# HF.net
KiCad netlist of a schematic drawn in Altium Designer
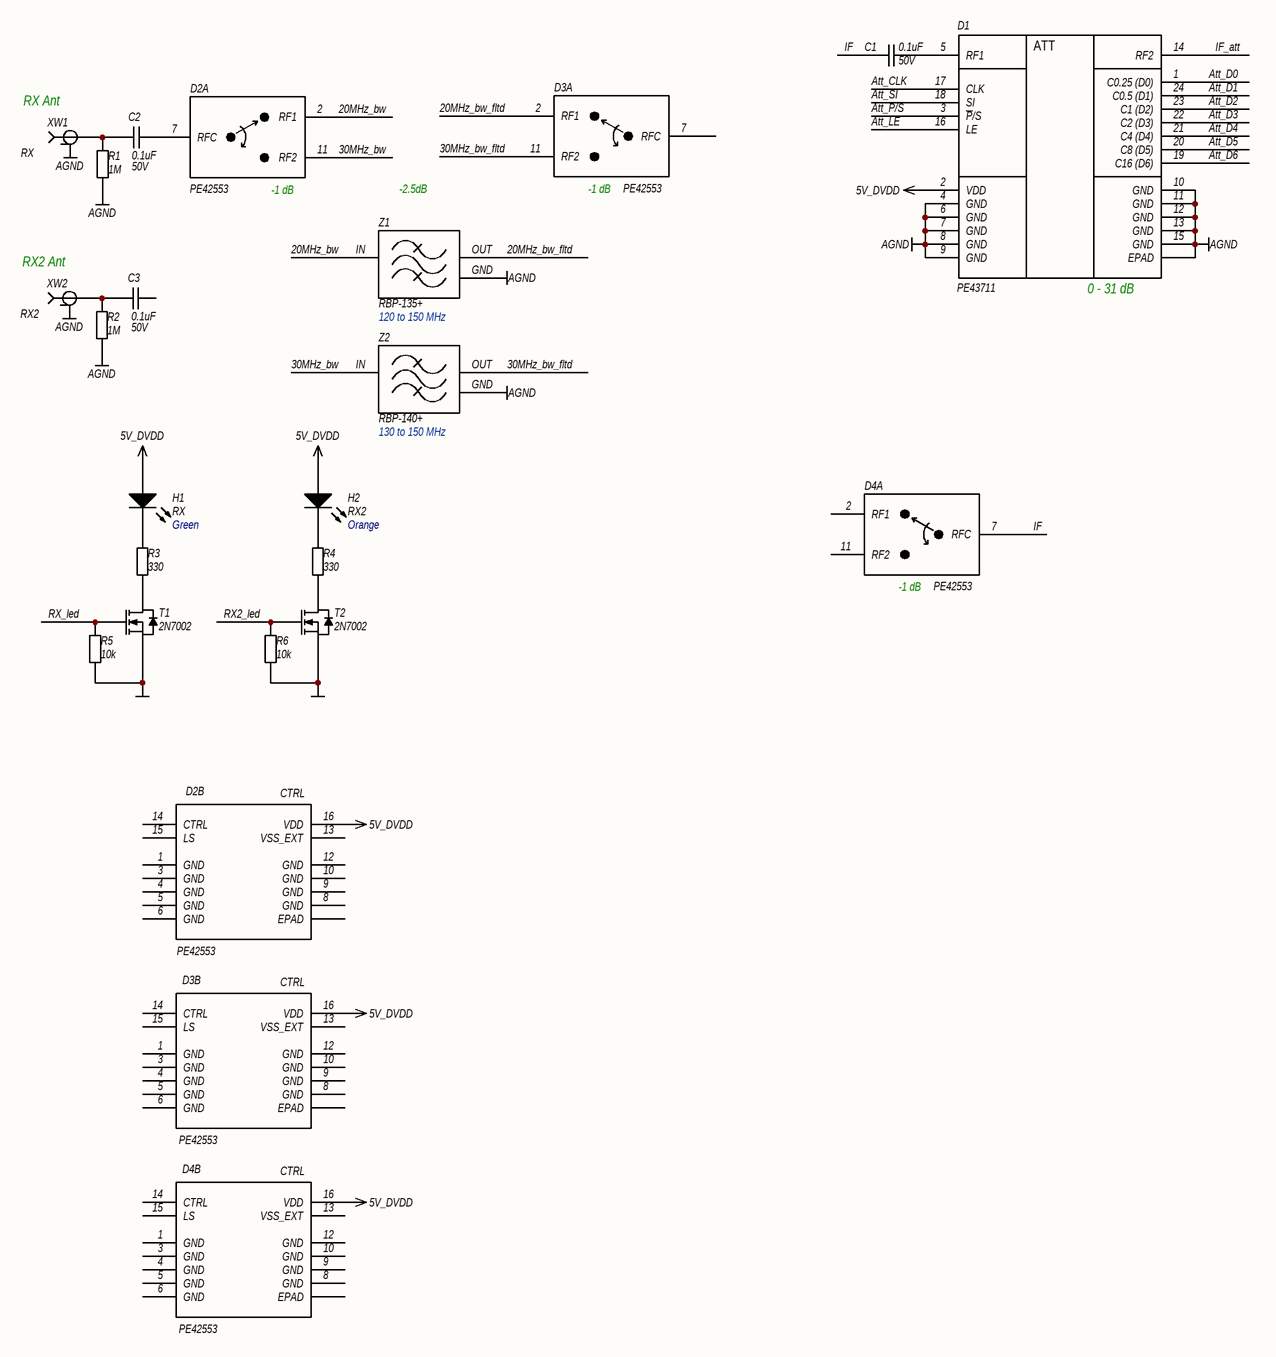
[diagram p0: HF.SchDoc]

(export (version "E")
  (design (tool "Eeschema 10.0.6"))
  (components
    (comp (ref "C1")
      (value "0.1uF")
      (footprint "C0402")
      (description "SMD Capacitor")
      (fields
        (field (name "MANUFACTURER") "Murata")
        (field (name "TOLERANCE") "10%")
        (field (name "VOLTAGE") "50V")
      )
      (libsource (lib "Kintex_SDR") (part "CAP"))
    )
    (comp (ref "C2")
      (value "0.1uF")
      (footprint "C0402")
      (description "SMD Capacitor")
      (fields
        (field (name "MANUFACTURER") "Murata")
        (field (name "TOLERANCE") "10%")
        (field (name "VOLTAGE") "50V")
      )
      (libsource (lib "Kintex_SDR") (part "CAP"))
    )
    (comp (ref "C3")
      (value "0.1uF")
      (footprint "C0402")
      (description "SMD Capacitor")
      (fields
        (field (name "MANUFACTURER") "Murata")
        (field (name "TOLERANCE") "10%")
        (field (name "VOLTAGE") "50V")
      )
      (libsource (lib "Kintex_SDR") (part "CAP"))
    )
    (comp (ref "D1")
      (value "PE43711")
      (footprint "QFN-24")
      (description "The PE43711 is a 50Ω, HaRP™ technology-enhanced, 7-bit RF digital step attenuator")
      (fields (field (name "MANUFACTURER") "Peregrine Technical Solutions"))
      (libsource (lib "DBLib") (part "PE43711"))
    )
    (comp (ref "D2")
      (value "PE42553")
      (footprint "QFN-16")
      (description "HaRPTM technology-enhanced absorptive SPDT")
      (fields (field (name "MANUFACTURER") "Peregrine Technical Solutions"))
      (libsource (lib "DBLib") (part "PE42553"))
    )
    (comp (ref "D3")
      (value "PE42553")
      (footprint "QFN-16")
      (description "HaRPTM technology-enhanced absorptive SPDT")
      (fields (field (name "MANUFACTURER") "Peregrine Technical Solutions"))
      (libsource (lib "") (part "PE42553_1"))
    )
    (comp (ref "D4")
      (value "PE42553")
      (footprint "QFN-16")
      (description "HaRPTM technology-enhanced absorptive SPDT")
      (fields (field (name "MANUFACTURER") "Peregrine Technical Solutions"))
      (libsource (lib "DBLib") (part "PE42553"))
    )
    (comp (ref "H1")
      (value "RX")
      (footprint "LED")
      (description "CHIP LED LAMP")
      (fields (field (name "MANUFACTURER") "Kingbright") (field (name "COLOR") "Green"))
      (libsource (lib "DBLib") (part "LED"))
    )
    (comp (ref "H2")
      (value "RX2")
      (footprint "LED")
      (description "CHIP LED LAMP")
      (fields (field (name "MANUFACTURER") "Kingbright") (field (name "COLOR") "Orange"))
      (libsource (lib "DBLib") (part "LED"))
    )
    (comp (ref "R1")
      (value "1M")
      (footprint "R0402")
      (description "SMD Resistor")
      (fields (field (name "POWER") "0.1 Wt") (field (name "TOLERANCE") "5%"))
      (libsource (lib "Kintex_SDR") (part "RES"))
    )
    (comp (ref "R2")
      (value "1M")
      (footprint "R0402")
      (description "SMD Resistor")
      (fields (field (name "POWER") "0.1 Wt") (field (name "TOLERANCE") "5%"))
      (libsource (lib "Kintex_SDR") (part "RES"))
    )
    (comp (ref "R3")
      (value "330")
      (footprint "R0805")
      (description "SMD Resistor")
      (fields (field (name "POWER") "0.125 Wt") (field (name "TOLERANCE") "5%"))
      (libsource (lib "Kintex_SDR") (part "RES"))
    )
    (comp (ref "R4")
      (value "330")
      (footprint "R0805")
      (description "SMD Resistor")
      (fields (field (name "POWER") "0.125 Wt") (field (name "TOLERANCE") "5%"))
      (libsource (lib "Kintex_SDR") (part "RES"))
    )
    (comp (ref "R5")
      (value "10k")
      (footprint "R0402")
      (description "SMD Resistor")
      (fields (field (name "POWER") "0.1 Wt") (field (name "TOLERANCE") "5%"))
      (libsource (lib "Kintex_SDR") (part "RES"))
    )
    (comp (ref "R6")
      (value "10k")
      (footprint "R0402")
      (description "SMD Resistor")
      (fields (field (name "POWER") "0.1 Wt") (field (name "TOLERANCE") "5%"))
      (libsource (lib "Kintex_SDR") (part "RES"))
    )
    (comp (ref "T1")
      (value "2N7002")
      (footprint "SOT-23")
      (description "N-Channel MOSFET 2N7002")
      (fields (field (name "VOLTAGE") "60V"))
      (libsource (lib "Kintex_SDR") (part "2N7002"))
    )
    (comp (ref "T2")
      (value "2N7002")
      (footprint "SOT-23")
      (description "N-Channel MOSFET 2N7002")
      (fields (field (name "VOLTAGE") "60V"))
      (libsource (lib "Kintex_SDR") (part "2N7002"))
    )
    (comp (ref "XW1")
      (value "RX")
      (footprint "MOLEX SD-73251-135 (Gold)")
      (description "50 Ohms, SMA Jack, Vertica")
      (fields (field (name "MANUFACTURER") "Molex"))
      (libsource (lib "DBLib") (part "RF Connector"))
    )
    (comp (ref "XW2")
      (value "RX2")
      (footprint "MOLEX SD-73251-135 (Gold)")
      (description "50 Ohms, SMA Jack, Vertica")
      (fields (field (name "MANUFACTURER") "Molex"))
      (libsource (lib "DBLib") (part "RF Connector"))
    )
    (comp (ref "Z1")
      (value "RBP-135+")
      (footprint "GP731")
      (description "Bandpass Filter")
      (fields (field (name "MANUFACTURER") "Mini-Circuits") (field (name "FREQUENCY") "120 to 150 MHz"))
      (libsource (lib "DBLib") (part "RBP-135+"))
    )
    (comp (ref "Z2")
      (value "RBP-140+")
      (footprint "GP731")
      (description "Bandpass Filter")
      (fields (field (name "MANUFACTURER") "Mini-Circuits") (field (name "FREQUENCY") "130 to 150 MHz"))
      (libsource (lib "DBLib") (part "RBP-140+"))
    )
  )
  (nets
    (net (code "1") (name "/20MHz_bw") (class "Default")
      (node (ref "D2") (pin "2") (pinfunction "RF1_2") (pintype "passive"))
      (node (ref "Z1") (pin "IN") (pinfunction "IN_IN") (pintype "passive"))
    )
    (net (code "2") (name "/20MHz_bw_fltd") (class "Default")
      (node (ref "D3") (pin "2") (pinfunction "RF1_2") (pintype "passive"))
      (node (ref "Z1") (pin "OUT") (pinfunction "OUT_OUT") (pintype "passive"))
    )
    (net (code "3") (name "/30MHz_bw") (class "Default")
      (node (ref "D2") (pin "11") (pinfunction "RF2_11") (pintype "passive"))
      (node (ref "Z2") (pin "IN") (pinfunction "IN_IN") (pintype "passive"))
    )
    (net (code "4") (name "/30MHz_bw_fltd") (class "Default")
      (node (ref "D3") (pin "11") (pinfunction "RF2_11") (pintype "passive"))
      (node (ref "Z2") (pin "OUT") (pinfunction "OUT_OUT") (pintype "passive"))
    )
    (net (code "5") (name "/Att_CLK") (class "Default")
      (node (ref "D1") (pin "17") (pinfunction "CLK_17") (pintype "passive"))
    )
    (net (code "6") (name "/Att_D0") (class "Default")
      (node (ref "D1") (pin "1") (pinfunction "C0.25_(D0)_1") (pintype "passive"))
    )
    (net (code "7") (name "/Att_D1") (class "Default")
      (node (ref "D1") (pin "24") (pinfunction "C0.5_(D1)_24") (pintype "passive"))
    )
    (net (code "8") (name "/Att_D2") (class "Default")
      (node (ref "D1") (pin "23") (pinfunction "C1_(D2)_23") (pintype "passive"))
    )
    (net (code "9") (name "/Att_D3") (class "Default")
      (node (ref "D1") (pin "22") (pinfunction "C2_(D3)_22") (pintype "passive"))
    )
    (net (code "10") (name "/Att_D4") (class "Default")
      (node (ref "D1") (pin "21") (pinfunction "C4_(D4)_21") (pintype "passive"))
    )
    (net (code "11") (name "/Att_D5") (class "Default")
      (node (ref "D1") (pin "20") (pinfunction "C8_(D5)_20") (pintype "passive"))
    )
    (net (code "12") (name "/Att_D6") (class "Default")
      (node (ref "D1") (pin "19") (pinfunction "C16_(D6)_19") (pintype "passive"))
    )
    (net (code "13") (name "/Att_LE") (class "Default")
      (node (ref "D1") (pin "16") (pinfunction "LE_16") (pintype "passive"))
    )
    (net (code "14") (name "/Att_P{slash}~{S}") (class "Default")
      (node (ref "D1") (pin "3") (pinfunction "~{P}/S_3") (pintype "passive"))
    )
    (net (code "15") (name "/Att_SI") (class "Default")
      (node (ref "D1") (pin "18") (pinfunction "SI_18") (pintype "passive"))
    )
    (net (code "16") (name "/IF") (class "Default")
      (node (ref "C1") (pin "1") (pinfunction "1_1") (pintype "passive"))
      (node (ref "D4") (pin "7") (pinfunction "RFC_7") (pintype "passive"))
    )
    (net (code "17") (name "/IF_att") (class "Default")
      (node (ref "D1") (pin "14") (pinfunction "RF2_14") (pintype "passive"))
    )
    (net (code "18") (name "/RX2_led") (class "Default")
      (node (ref "R6") (pin "1") (pinfunction "1_1") (pintype "passive"))
      (node (ref "T2") (pin "1") (pinfunction "G_1") (pintype "passive"))
    )
    (net (code "19") (name "/RX_led") (class "Default")
      (node (ref "R5") (pin "1") (pinfunction "1_1") (pintype "passive"))
      (node (ref "T1") (pin "1") (pinfunction "G_1") (pintype "passive"))
    )
    (net (code "20") (name "5V_DVDD") (class "Default")
      (node (ref "D1") (pin "2") (pinfunction "VDD_2") (pintype "passive"))
      (node (ref "D2") (pin "16") (pinfunction "VDD_16") (pintype "passive"))
      (node (ref "D3") (pin "16") (pinfunction "VDD_16") (pintype "passive"))
      (node (ref "D4") (pin "16") (pinfunction "VDD_16") (pintype "passive"))
      (node (ref "H1") (pin "2") (pinfunction "A_2") (pintype "passive"))
      (node (ref "H2") (pin "2") (pinfunction "A_2") (pintype "passive"))
    )
    (net (code "21") (name "AGND") (class "Default")
      (node (ref "D1") (pin "10") (pinfunction "GND_10") (pintype "passive"))
      (node (ref "D1") (pin "11") (pinfunction "GND_11") (pintype "passive"))
      (node (ref "D1") (pin "12") (pinfunction "GND_12") (pintype "passive"))
      (node (ref "D1") (pin "13") (pinfunction "GND_13") (pintype "passive"))
      (node (ref "D1") (pin "15") (pinfunction "GND_15") (pintype "passive"))
      (node (ref "D1") (pin "25") (pinfunction "EPAD_25") (pintype "passive"))
      (node (ref "D1") (pin "4") (pinfunction "GND_4") (pintype "passive"))
      (node (ref "D1") (pin "6") (pinfunction "GND_6") (pintype "passive"))
      (node (ref "D1") (pin "7") (pinfunction "GND_7") (pintype "passive"))
      (node (ref "D1") (pin "8") (pinfunction "GND_8") (pintype "passive"))
      (node (ref "D1") (pin "9") (pinfunction "GND_9") (pintype "passive"))
      (node (ref "R1") (pin "2") (pinfunction "2_2") (pintype "passive"))
      (node (ref "R2") (pin "2") (pinfunction "2_2") (pintype "passive"))
      (node (ref "XW1") (pin "G") (pinfunction "GND_G") (pintype "passive"))
      (node (ref "XW2") (pin "G") (pinfunction "GND_G") (pintype "passive"))
      (node (ref "Z1") (pin "GND") (pinfunction "GND_GND") (pintype "passive"))
      (node (ref "Z2") (pin "GND") (pinfunction "GND_GND") (pintype "passive"))
    )
    (net (code "22") (name "GND") (class "Default")
      (node (ref "R5") (pin "2") (pinfunction "2_2") (pintype "passive"))
      (node (ref "R6") (pin "2") (pinfunction "2_2") (pintype "passive"))
      (node (ref "T1") (pin "2") (pinfunction "S_2") (pintype "passive"))
      (node (ref "T2") (pin "2") (pinfunction "S_2") (pintype "passive"))
    )
    (net (code "23") (name "Net-(D1-RF1)") (class "Default")
      (node (ref "C1") (pin "2") (pinfunction "2_2") (pintype "passive"))
      (node (ref "D1") (pin "5") (pinfunction "RF1_5") (pintype "passive"))
    )
    (net (code "24") (name "Net-(D2A-RFC)") (class "Default")
      (node (ref "C2") (pin "2") (pinfunction "2_2") (pintype "passive"))
      (node (ref "D2") (pin "7") (pinfunction "RFC_7") (pintype "passive"))
    )
    (net (code "25") (name "Net-(H1-K)") (class "Default")
      (node (ref "H1") (pin "1") (pinfunction "K_1") (pintype "passive"))
      (node (ref "R3") (pin "1") (pinfunction "1_1") (pintype "passive"))
    )
    (net (code "26") (name "Net-(H2-K)") (class "Default")
      (node (ref "H2") (pin "1") (pinfunction "K_1") (pintype "passive"))
      (node (ref "R4") (pin "1") (pinfunction "1_1") (pintype "passive"))
    )
    (net (code "27") (name "Net-(T1-D)") (class "Default")
      (node (ref "R3") (pin "2") (pinfunction "2_2") (pintype "passive"))
      (node (ref "T1") (pin "3") (pinfunction "D_3") (pintype "passive"))
    )
    (net (code "28") (name "Net-(T2-D)") (class "Default")
      (node (ref "R4") (pin "2") (pinfunction "2_2") (pintype "passive"))
      (node (ref "T2") (pin "3") (pinfunction "D_3") (pintype "passive"))
    )
    (net (code "29") (name "Net-(XW1-RF)") (class "Default")
      (node (ref "C2") (pin "1") (pinfunction "1_1") (pintype "passive"))
      (node (ref "R1") (pin "1") (pinfunction "1_1") (pintype "passive"))
      (node (ref "XW1") (pin "S") (pinfunction "RF_S") (pintype "passive"))
    )
    (net (code "30") (name "Net-(XW2-RF)") (class "Default")
      (node (ref "C3") (pin "1") (pinfunction "1_1") (pintype "passive"))
      (node (ref "R2") (pin "1") (pinfunction "1_1") (pintype "passive"))
      (node (ref "XW2") (pin "S") (pinfunction "RF_S") (pintype "passive"))
    )
    (net (code "31") (name "unconnected-(C3-Pad2)") (class "Default")
      (node (ref "C3") (pin "2") (pinfunction "2_2") (pintype "passive"))
    )
    (net (code "32") (name "unconnected-(D2B-CTRL-Pad14)") (class "Default")
      (node (ref "D2") (pin "14") (pinfunction "CTRL_14") (pintype "passive"))
    )
    (net (code "33") (name "unconnected-(D2B-EPAD-Pad17)") (class "Default")
      (node (ref "D2") (pin "17") (pinfunction "EPAD_17") (pintype "passive"))
    )
    (net (code "34") (name "unconnected-(D2B-GND-Pad1)") (class "Default")
      (node (ref "D2") (pin "1") (pinfunction "GND_1") (pintype "passive"))
    )
    (net (code "35") (name "unconnected-(D2B-GND-Pad3)") (class "Default")
      (node (ref "D2") (pin "3") (pinfunction "GND_3") (pintype "passive"))
    )
    (net (code "36") (name "unconnected-(D2B-GND-Pad4)") (class "Default")
      (node (ref "D2") (pin "4") (pinfunction "GND_4") (pintype "passive"))
    )
    (net (code "37") (name "unconnected-(D2B-GND-Pad5)") (class "Default")
      (node (ref "D2") (pin "5") (pinfunction "GND_5") (pintype "passive"))
    )
    (net (code "38") (name "unconnected-(D2B-GND-Pad6)") (class "Default")
      (node (ref "D2") (pin "6") (pinfunction "GND_6") (pintype "passive"))
    )
    (net (code "39") (name "unconnected-(D2B-GND-Pad8)") (class "Default")
      (node (ref "D2") (pin "8") (pinfunction "GND_8") (pintype "passive"))
    )
    (net (code "40") (name "unconnected-(D2B-GND-Pad9)") (class "Default")
      (node (ref "D2") (pin "9") (pinfunction "GND_9") (pintype "passive"))
    )
    (net (code "41") (name "unconnected-(D2B-GND-Pad10)") (class "Default")
      (node (ref "D2") (pin "10") (pinfunction "GND_10") (pintype "passive"))
    )
    (net (code "42") (name "unconnected-(D2B-GND-Pad12)") (class "Default")
      (node (ref "D2") (pin "12") (pinfunction "GND_12") (pintype "passive"))
    )
    (net (code "43") (name "unconnected-(D2B-LS-Pad15)") (class "Default")
      (node (ref "D2") (pin "15") (pinfunction "LS_15") (pintype "passive"))
    )
    (net (code "44") (name "unconnected-(D2B-VSS_EXT-Pad13)") (class "Default")
      (node (ref "D2") (pin "13") (pinfunction "VSS_EXT_13") (pintype "passive"))
    )
    (net (code "45") (name "unconnected-(D3A-RFC-Pad7)") (class "Default")
      (node (ref "D3") (pin "7") (pinfunction "RFC_7") (pintype "passive"))
    )
    (net (code "46") (name "unconnected-(D3B-CTRL-Pad14)") (class "Default")
      (node (ref "D3") (pin "14") (pinfunction "CTRL_14") (pintype "passive"))
    )
    (net (code "47") (name "unconnected-(D3B-EPAD-Pad17)") (class "Default")
      (node (ref "D3") (pin "17") (pinfunction "EPAD_17") (pintype "passive"))
    )
    (net (code "48") (name "unconnected-(D3B-GND-Pad1)") (class "Default")
      (node (ref "D3") (pin "1") (pinfunction "GND_1") (pintype "passive"))
    )
    (net (code "49") (name "unconnected-(D3B-GND-Pad3)") (class "Default")
      (node (ref "D3") (pin "3") (pinfunction "GND_3") (pintype "passive"))
    )
    (net (code "50") (name "unconnected-(D3B-GND-Pad4)") (class "Default")
      (node (ref "D3") (pin "4") (pinfunction "GND_4") (pintype "passive"))
    )
    (net (code "51") (name "unconnected-(D3B-GND-Pad5)") (class "Default")
      (node (ref "D3") (pin "5") (pinfunction "GND_5") (pintype "passive"))
    )
    (net (code "52") (name "unconnected-(D3B-GND-Pad6)") (class "Default")
      (node (ref "D3") (pin "6") (pinfunction "GND_6") (pintype "passive"))
    )
    (net (code "53") (name "unconnected-(D3B-GND-Pad8)") (class "Default")
      (node (ref "D3") (pin "8") (pinfunction "GND_8") (pintype "passive"))
    )
    (net (code "54") (name "unconnected-(D3B-GND-Pad9)") (class "Default")
      (node (ref "D3") (pin "9") (pinfunction "GND_9") (pintype "passive"))
    )
    (net (code "55") (name "unconnected-(D3B-GND-Pad10)") (class "Default")
      (node (ref "D3") (pin "10") (pinfunction "GND_10") (pintype "passive"))
    )
    (net (code "56") (name "unconnected-(D3B-GND-Pad12)") (class "Default")
      (node (ref "D3") (pin "12") (pinfunction "GND_12") (pintype "passive"))
    )
    (net (code "57") (name "unconnected-(D3B-LS-Pad15)") (class "Default")
      (node (ref "D3") (pin "15") (pinfunction "LS_15") (pintype "passive"))
    )
    (net (code "58") (name "unconnected-(D3B-VSS_EXT-Pad13)") (class "Default")
      (node (ref "D3") (pin "13") (pinfunction "VSS_EXT_13") (pintype "passive"))
    )
    (net (code "59") (name "unconnected-(D4A-RF1-Pad2)") (class "Default")
      (node (ref "D4") (pin "2") (pinfunction "RF1_2") (pintype "passive"))
    )
    (net (code "60") (name "unconnected-(D4A-RF2-Pad11)") (class "Default")
      (node (ref "D4") (pin "11") (pinfunction "RF2_11") (pintype "passive"))
    )
    (net (code "61") (name "unconnected-(D4B-CTRL-Pad14)") (class "Default")
      (node (ref "D4") (pin "14") (pinfunction "CTRL_14") (pintype "passive"))
    )
    (net (code "62") (name "unconnected-(D4B-EPAD-Pad17)") (class "Default")
      (node (ref "D4") (pin "17") (pinfunction "EPAD_17") (pintype "passive"))
    )
    (net (code "63") (name "unconnected-(D4B-GND-Pad1)") (class "Default")
      (node (ref "D4") (pin "1") (pinfunction "GND_1") (pintype "passive"))
    )
    (net (code "64") (name "unconnected-(D4B-GND-Pad3)") (class "Default")
      (node (ref "D4") (pin "3") (pinfunction "GND_3") (pintype "passive"))
    )
    (net (code "65") (name "unconnected-(D4B-GND-Pad4)") (class "Default")
      (node (ref "D4") (pin "4") (pinfunction "GND_4") (pintype "passive"))
    )
    (net (code "66") (name "unconnected-(D4B-GND-Pad5)") (class "Default")
      (node (ref "D4") (pin "5") (pinfunction "GND_5") (pintype "passive"))
    )
    (net (code "67") (name "unconnected-(D4B-GND-Pad6)") (class "Default")
      (node (ref "D4") (pin "6") (pinfunction "GND_6") (pintype "passive"))
    )
    (net (code "68") (name "unconnected-(D4B-GND-Pad8)") (class "Default")
      (node (ref "D4") (pin "8") (pinfunction "GND_8") (pintype "passive"))
    )
    (net (code "69") (name "unconnected-(D4B-GND-Pad9)") (class "Default")
      (node (ref "D4") (pin "9") (pinfunction "GND_9") (pintype "passive"))
    )
    (net (code "70") (name "unconnected-(D4B-GND-Pad10)") (class "Default")
      (node (ref "D4") (pin "10") (pinfunction "GND_10") (pintype "passive"))
    )
    (net (code "71") (name "unconnected-(D4B-GND-Pad12)") (class "Default")
      (node (ref "D4") (pin "12") (pinfunction "GND_12") (pintype "passive"))
    )
    (net (code "72") (name "unconnected-(D4B-LS-Pad15)") (class "Default")
      (node (ref "D4") (pin "15") (pinfunction "LS_15") (pintype "passive"))
    )
    (net (code "73") (name "unconnected-(D4B-VSS_EXT-Pad13)") (class "Default")
      (node (ref "D4") (pin "13") (pinfunction "VSS_EXT_13") (pintype "passive"))
    )
  )
)
